# SCH_Relatorio2-ProjRoboticos_2026-09-19.net
KiCad netlist of a schematic drawn in EasyEDA
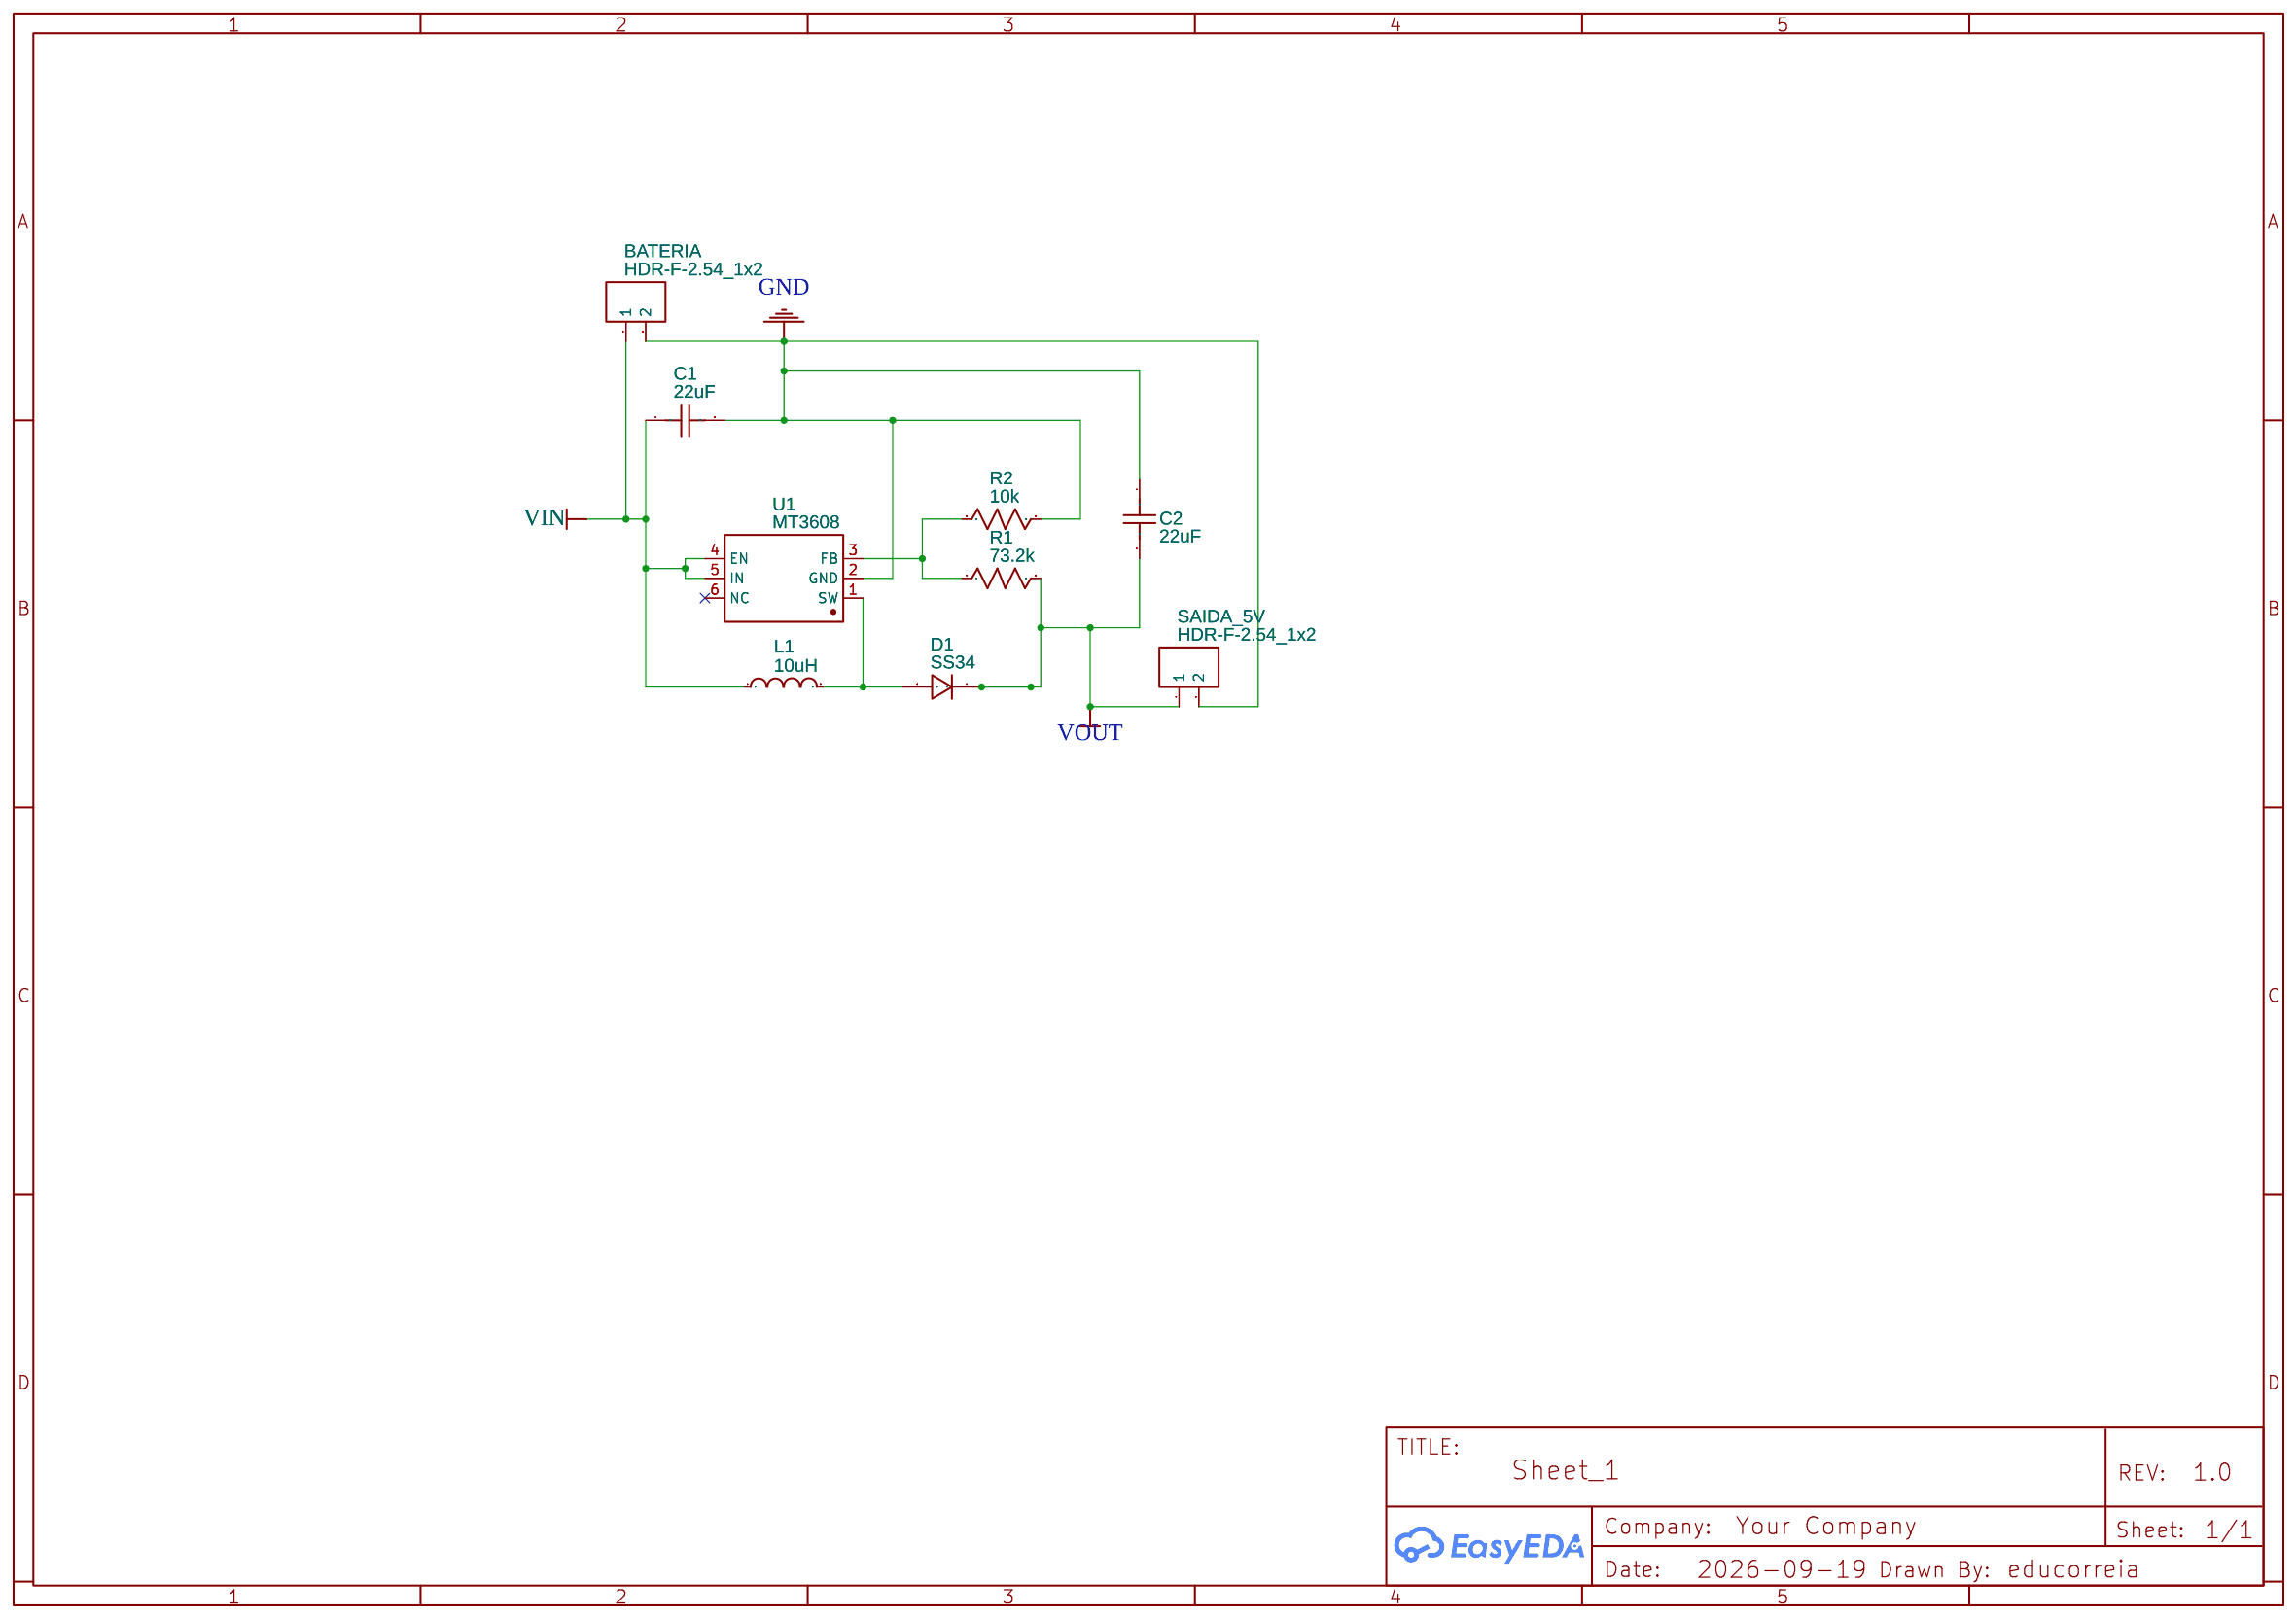
[diagram p0: schematic sheet]

(export (version "E")
  (design (tool "Eeschema 10.0.6"))
  (components
    (comp (ref "BATERIA") (value "HDR-F-2.54_1x2") (libsource (lib "") (part "HDR-F-2.54_1x2")))
    (comp (ref "C1") (value "22uF") (libsource (lib "") (part "C_0603_US_1")))
    (comp (ref "C2") (value "22uF") (libsource (lib "") (part "C_0603_US")))
    (comp (ref "D1")
      (value "SS34")
      (fields (field (name "Manufacturer Part") "1N4007W") (field (name "Manufacturer") "BLUE ROCKET"))
      (libsource (lib "") (part "1N4007W"))
    )
    (comp (ref "L1") (value "10uH") (libsource (lib "") (part "L0603_US")))
    (comp (ref "R1") (value "73.2k") (libsource (lib "") (part "R_0603_US")))
    (comp (ref "R2") (value "10k") (libsource (lib "") (part "R_0603_US")))
    (comp (ref "SAIDA_5V") (value "HDR-F-2.54_1x2") (libsource (lib "") (part "HDR-F-2.54_1x2_1")))
    (comp (ref "U1")
      (value "MT3608")
      (fields (field (name "Manufacturer") "西安航天民芯"))
      (libsource (lib "") (part "MT3608"))
    )
  )
  (nets
    (net (code "1") (name "GND") (class "Default")
      (node (ref "BATERIA") (pin "2") (pinfunction "2_2") (pintype "input"))
      (node (ref "C1") (pin "2") (pinfunction "2_2") (pintype "unspecified"))
      (node (ref "C2") (pin "1") (pinfunction "1_1") (pintype "unspecified"))
      (node (ref "R2") (pin "2") (pinfunction "2_2") (pintype "unspecified"))
      (node (ref "SAIDA_5V") (pin "2") (pinfunction "2_2") (pintype "input"))
      (node (ref "U1") (pin "2") (pinfunction "GND_2") (pintype "unspecified"))
    )
    (net (code "2") (name "Net-(U1-FB)") (class "Default")
      (node (ref "R1") (pin "1") (pinfunction "1_1") (pintype "unspecified"))
      (node (ref "R2") (pin "1") (pinfunction "1_1") (pintype "unspecified"))
      (node (ref "U1") (pin "3") (pinfunction "FB_3") (pintype "unspecified"))
    )
    (net (code "3") (name "Net-(U1-SW)") (class "Default")
      (node (ref "D1") (pin "2") (pinfunction "2_2") (pintype "unspecified"))
      (node (ref "L1") (pin "2") (pinfunction "2_2") (pintype "unspecified"))
      (node (ref "U1") (pin "1") (pinfunction "SW_1") (pintype "unspecified"))
    )
    (net (code "4") (name "VIN") (class "Default")
      (node (ref "BATERIA") (pin "1") (pinfunction "1_1") (pintype "input"))
      (node (ref "C1") (pin "1") (pinfunction "1_1") (pintype "unspecified"))
      (node (ref "L1") (pin "1") (pinfunction "1_1") (pintype "unspecified"))
      (node (ref "U1") (pin "4") (pinfunction "EN_4") (pintype "unspecified"))
      (node (ref "U1") (pin "5") (pinfunction "IN_5") (pintype "unspecified"))
    )
    (net (code "5") (name "VOUT") (class "Default")
      (node (ref "C2") (pin "2") (pinfunction "2_2") (pintype "unspecified"))
      (node (ref "D1") (pin "1") (pinfunction "1_1") (pintype "unspecified"))
      (node (ref "R1") (pin "2") (pinfunction "2_2") (pintype "unspecified"))
      (node (ref "SAIDA_5V") (pin "1") (pinfunction "1_1") (pintype "input"))
    )
    (net (code "6") (name "unconnected-(U1-NC-Pad6)") (class "Default")
      (node (ref "U1") (pin "6") (pinfunction "NC_6") (pintype "unspecified+no_connect"))
    )
  )
)
